# Final_6_2_1.net
KiCad netlist of a schematic drawn in EAGLE
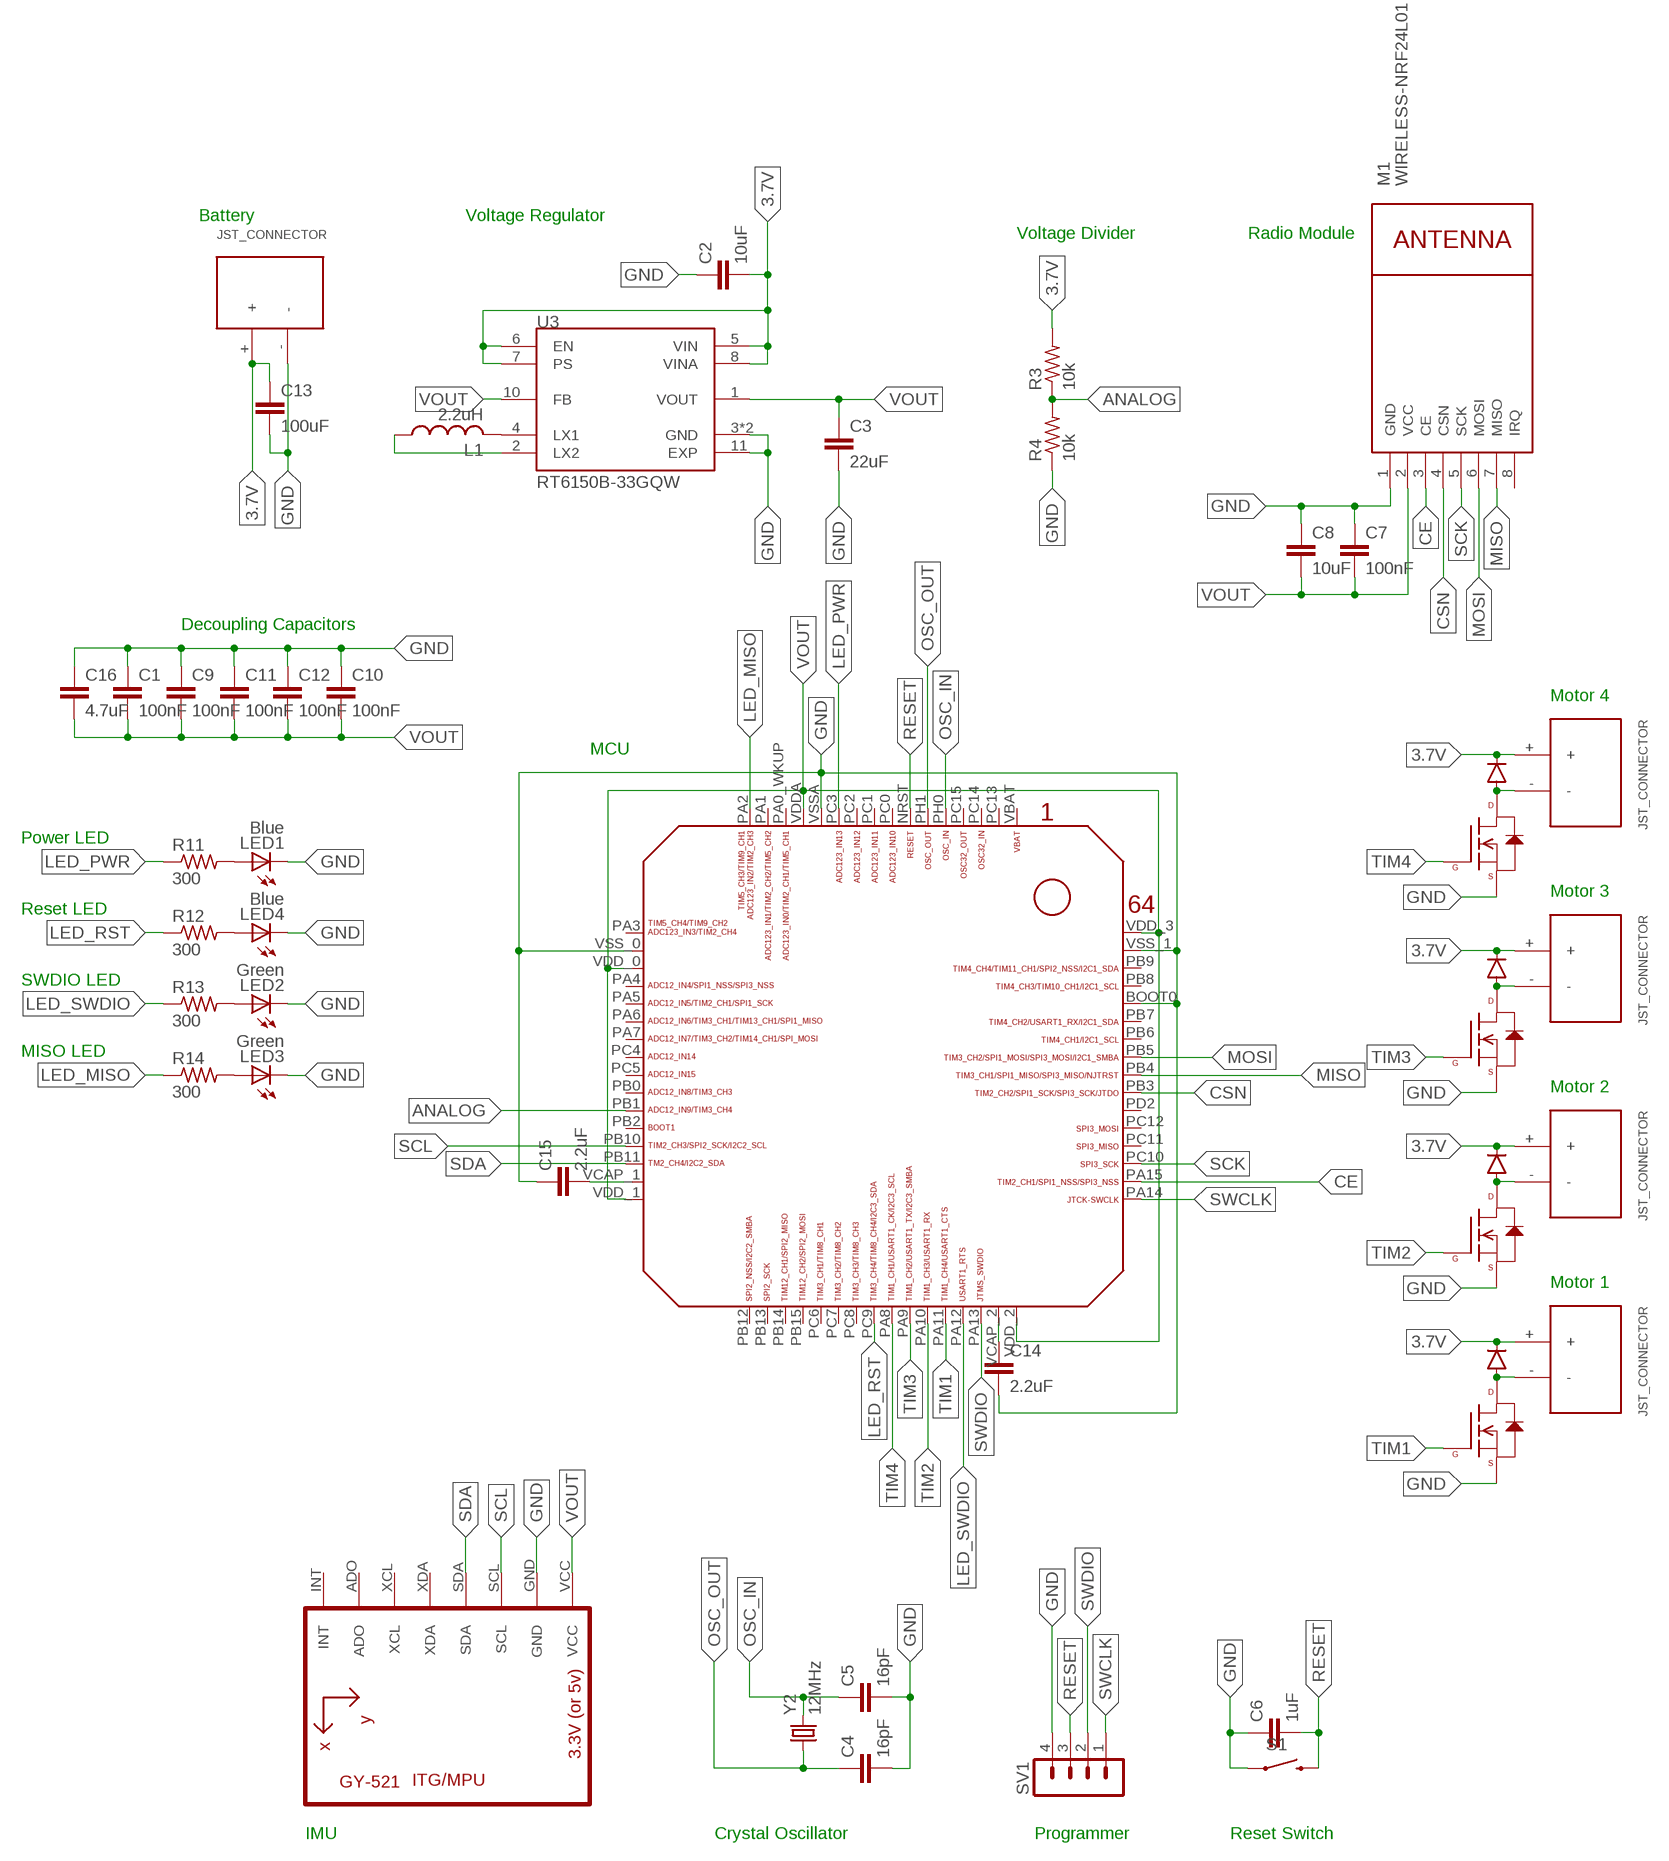
[diagram p0: schematic, sheet 1]

(export (version "E")
  (design (tool "Eeschema 10.0.6"))
  (components
    (comp (ref "C1")
      (value "100nF")
      (footprint "eagle-import:C0603")
      (libsource (lib "eagle-import") (part "rcl_334_C-EUC0603"))
    )
    (comp (ref "C2")
      (value "10uF")
      (footprint "eagle-import:C0603")
      (libsource (lib "eagle-import") (part "rcl_334_C-EUC0603"))
    )
    (comp (ref "C3")
      (value "22uF")
      (footprint "eagle-import:C0603")
      (libsource (lib "eagle-import") (part "rcl_334_C-EUC0603"))
    )
    (comp (ref "C4")
      (value "16pF")
      (footprint "eagle-import:C0603")
      (libsource (lib "eagle-import") (part "rcl_334_C-EUC0603"))
    )
    (comp (ref "C5")
      (value "16pF")
      (footprint "eagle-import:C0603")
      (libsource (lib "eagle-import") (part "rcl_334_C-EUC0603"))
    )
    (comp (ref "C6")
      (value "1uF")
      (footprint "eagle-import:C0603")
      (libsource (lib "eagle-import") (part "rcl_334_C-EUC0603"))
    )
    (comp (ref "C7")
      (value "100nF")
      (footprint "eagle-import:C0603")
      (libsource (lib "eagle-import") (part "rcl_334_C-EUC0603"))
    )
    (comp (ref "C8")
      (value "10uF")
      (footprint "eagle-import:C0603")
      (libsource (lib "eagle-import") (part "rcl_334_C-EUC0603"))
    )
    (comp (ref "C9")
      (value "100nF")
      (footprint "eagle-import:C0603")
      (libsource (lib "eagle-import") (part "rcl_334_C-EUC0603"))
    )
    (comp (ref "C10")
      (value "100nF")
      (footprint "eagle-import:C0603")
      (libsource (lib "eagle-import") (part "rcl_334_C-EUC0603"))
    )
    (comp (ref "C11")
      (value "100nF")
      (footprint "eagle-import:C0603")
      (libsource (lib "eagle-import") (part "rcl_334_C-EUC0603"))
    )
    (comp (ref "C12")
      (value "100nF")
      (footprint "eagle-import:C0603")
      (libsource (lib "eagle-import") (part "rcl_334_C-EUC0603"))
    )
    (comp (ref "C13")
      (value "100uF")
      (footprint "eagle-import:C1206")
      (libsource (lib "eagle-import") (part "rcl_334_C-EUC1206"))
    )
    (comp (ref "C14")
      (value "2.2uF")
      (footprint "eagle-import:C0603")
      (libsource (lib "eagle-import") (part "C-EUC0603"))
    )
    (comp (ref "C15")
      (value "2.2uF")
      (footprint "eagle-import:C0603")
      (libsource (lib "eagle-import") (part "C-EUC0603"))
    )
    (comp (ref "C16")
      (value "4.7uF")
      (footprint "eagle-import:C0603")
      (libsource (lib "eagle-import") (part "rcl_334_C-EUC0603"))
    )
    (comp (ref "L1")
      (value "2.2uH")
      (footprint "eagle-import:L0603")
      (libsource (lib "eagle-import") (part "L-USL0603"))
    )
    (comp (ref "LED1")
      (value "Blue")
      (footprint "eagle-import:CHIP-LED0603")
      (libsource (lib "eagle-import") (part "LEDCHIP-LED0603"))
    )
    (comp (ref "LED2")
      (value "Green")
      (footprint "eagle-import:CHIP-LED0603")
      (libsource (lib "eagle-import") (part "LEDCHIP-LED0603"))
    )
    (comp (ref "LED3")
      (value "Green")
      (footprint "eagle-import:CHIP-LED0603")
      (libsource (lib "eagle-import") (part "LEDCHIP-LED0603"))
    )
    (comp (ref "LED4")
      (value "Blue")
      (footprint "eagle-import:CHIP-LED0603")
      (libsource (lib "eagle-import") (part "LEDCHIP-LED0603"))
    )
    (comp (ref "M1")
      (value "WIRELESS-NRF24L01")
      (footprint "eagle-import:WIRELESS-NRF24L01")
      (libsource (lib "eagle-import") (part "WIRELESS-NRF24L01"))
    )
    (comp (ref "R3")
      (value "10k")
      (footprint "eagle-import:R0603")
      (libsource (lib "eagle-import") (part "R-US_R0603"))
    )
    (comp (ref "R4")
      (value "10k")
      (footprint "eagle-import:R0603")
      (libsource (lib "eagle-import") (part "R-US_R0603"))
    )
    (comp (ref "R11")
      (value "300")
      (footprint "eagle-import:R0603")
      (libsource (lib "eagle-import") (part "R-US_R0603"))
    )
    (comp (ref "R12")
      (value "300")
      (footprint "eagle-import:R0603")
      (libsource (lib "eagle-import") (part "R-US_R0603"))
    )
    (comp (ref "R13")
      (value "300")
      (footprint "eagle-import:R0603")
      (libsource (lib "eagle-import") (part "R-US_R0603"))
    )
    (comp (ref "R14")
      (value "300")
      (footprint "eagle-import:R0603")
      (libsource (lib "eagle-import") (part "R-US_R0603"))
    )
    (comp (ref "S1")
      (value "SWITCH-MOMENTARY-2SMD")
      (footprint "eagle-import:TACTILE-SWITCH-SMD")
      (libsource (lib "eagle-import") (part "SWITCH-MOMENTARY-2SMD"))
    )
    (comp (ref "SV1")
      (value "MA04-1")
      (footprint "eagle-import:MA04-1")
      (libsource (lib "eagle-import") (part "MA04-1"))
    )
    (comp (ref "U$1")
      (value "STM32F405/415_LQFP64")
      (footprint "eagle-import:STM32F405_415_LQFP64")
      (libsource (lib "eagle-import") (part "STM32F405/415_LQFP64"))
    )
    (comp (ref "U$2")
      (value "JST_CONNECTOR_FEMALE")
      (footprint "eagle-import:JST_CONNECTOR_FEMALE")
      (libsource (lib "eagle-import") (part "JST_CONNECTOR_FEMALE"))
    )
    (comp (ref "U$3")
      (value "JST_CONNECTOR_FEMALE")
      (footprint "eagle-import:JST_CONNECTOR_FEMALE")
      (libsource (lib "eagle-import") (part "JST_CONNECTOR_FEMALE"))
    )
    (comp (ref "U$4")
      (value "JST_CONNECTOR_FEMALE")
      (footprint "eagle-import:JST_CONNECTOR_FEMALE")
      (libsource (lib "eagle-import") (part "JST_CONNECTOR_FEMALE"))
    )
    (comp (ref "U$5")
      (value "JST_CONNECTOR_FEMALE")
      (footprint "eagle-import:JST_CONNECTOR_FEMALE")
      (libsource (lib "eagle-import") (part "JST_CONNECTOR_FEMALE"))
    )
    (comp (ref "U$6")
      (value "JST_CONNECTOR_FEMALE")
      (footprint "eagle-import:JST_CONNECTOR_FEMALE")
      (libsource (lib "eagle-import") (part "JST_CONNECTOR_FEMALE"))
    )
    (comp (ref "U$7")
      (value "N-CHANNEL-MOSFET-IRLML6244TRPBF")
      (footprint "eagle-import:SOT23-3")
      (libsource (lib "eagle-import") (part "N-CHANNEL-MOSFET-IRLML6244TRPBF"))
    )
    (comp (ref "U$8")
      (value "N-CHANNEL-MOSFET-IRLML6244TRPBF")
      (footprint "eagle-import:SOT23-3")
      (libsource (lib "eagle-import") (part "N-CHANNEL-MOSFET-IRLML6244TRPBF"))
    )
    (comp (ref "U$9")
      (value "N-CHANNEL-MOSFET-IRLML6244TRPBF")
      (footprint "eagle-import:SOT23-3")
      (libsource (lib "eagle-import") (part "N-CHANNEL-MOSFET-IRLML6244TRPBF"))
    )
    (comp (ref "U$10")
      (value "N-CHANNEL-MOSFET-IRLML6244TRPBF")
      (footprint "eagle-import:SOT23-3")
      (libsource (lib "eagle-import") (part "N-CHANNEL-MOSFET-IRLML6244TRPBF"))
    )
    (comp (ref "U$11")
      (value "DB2W40300L")
      (footprint "eagle-import:MINI2-F3-B")
      (libsource (lib "eagle-import") (part "DB2W40300L"))
    )
    (comp (ref "U$12")
      (value "DB2W40300L")
      (footprint "eagle-import:MINI2-F3-B")
      (libsource (lib "eagle-import") (part "DB2W40300L"))
    )
    (comp (ref "U$13")
      (value "DB2W40300L")
      (footprint "eagle-import:MINI2-F3-B")
      (libsource (lib "eagle-import") (part "DB2W40300L"))
    )
    (comp (ref "U$14")
      (value "DB2W40300L")
      (footprint "eagle-import:MINI2-F3-B")
      (libsource (lib "eagle-import") (part "DB2W40300L"))
    )
    (comp (ref "U2")
      (value "GY-521MPU6050")
      (footprint "eagle-import:GY-521")
      (libsource (lib "eagle-import") (part "GY-521MPU6050"))
    )
    (comp (ref "U3")
      (value "RT6150B-33GQW")
      (footprint "eagle-import:SON50P250X250X80-11N")
      (fields (field (name "DIGI-KEY_PART_NUMBER") "RT6150B-33GQWCT-ND") (field (name "MF") "Richtek USA"))
      (libsource (lib "eagle-import") (part "RT6150B-33GQW"))
    )
    (comp (ref "Y2")
      (value "12MHz")
      (footprint "eagle-import:HC49UP")
      (libsource (lib "eagle-import") (part "CRYSTALSMD"))
    )
  )
  (nets
    (net (code "1") (name "3.7V") (class "Default")
      (node (ref "C13") (pin "1") (pinfunction "1_1") (pintype "passive"))
      (node (ref "C2") (pin "2") (pinfunction "2_2") (pintype "passive"))
      (node (ref "R3") (pin "2") (pinfunction "2_2") (pintype "passive"))
      (node (ref "U$11") (pin "NEG") (pinfunction "GPIN_NEG") (pintype "passive"))
      (node (ref "U$12") (pin "NEG") (pinfunction "GPIN_NEG") (pintype "passive"))
      (node (ref "U$13") (pin "NEG") (pinfunction "GPIN_NEG") (pintype "passive"))
      (node (ref "U$14") (pin "NEG") (pinfunction "GPIN_NEG") (pintype "passive"))
      (node (ref "U$2") (pin "+") (pinfunction "+_+") (pintype "bidirectional"))
      (node (ref "U$3") (pin "+") (pinfunction "+_+") (pintype "bidirectional"))
      (node (ref "U$4") (pin "+") (pinfunction "+_+") (pintype "bidirectional"))
      (node (ref "U$5") (pin "+") (pinfunction "+_+") (pintype "bidirectional"))
      (node (ref "U$6") (pin "+") (pinfunction "+_+") (pintype "bidirectional"))
      (node (ref "U3") (pin "5") (pinfunction "VIN_5") (pintype "power_in"))
      (node (ref "U3") (pin "6") (pinfunction "EN_6") (pintype "input"))
      (node (ref "U3") (pin "7") (pinfunction "PS_7") (pintype "input"))
      (node (ref "U3") (pin "8") (pinfunction "VINA_8") (pintype "power_in"))
    )
    (net (code "2") (name "ANALOG") (class "Default")
      (node (ref "R3") (pin "1") (pinfunction "1_1") (pintype "passive"))
      (node (ref "R4") (pin "2") (pinfunction "2_2") (pintype "passive"))
      (node (ref "U$1") (pin "PB1") (pinfunction "PB1_PB1") (pintype "bidirectional"))
    )
    (net (code "3") (name "CE") (class "Default")
      (node (ref "M1") (pin "3") (pinfunction "CE_3") (pintype "bidirectional"))
      (node (ref "U$1") (pin "PA15") (pinfunction "PA15_PA15") (pintype "bidirectional"))
    )
    (net (code "4") (name "CSN") (class "Default")
      (node (ref "M1") (pin "4") (pinfunction "CSN_4") (pintype "bidirectional"))
      (node (ref "U$1") (pin "PB3") (pinfunction "PB3_PB3") (pintype "bidirectional"))
    )
    (net (code "5") (name "GND") (class "Default")
      (node (ref "C1") (pin "1") (pinfunction "1_1") (pintype "passive"))
      (node (ref "C10") (pin "1") (pinfunction "1_1") (pintype "passive"))
      (node (ref "C11") (pin "1") (pinfunction "1_1") (pintype "passive"))
      (node (ref "C12") (pin "1") (pinfunction "1_1") (pintype "passive"))
      (node (ref "C13") (pin "2") (pinfunction "2_2") (pintype "passive"))
      (node (ref "C14") (pin "2") (pinfunction "2_2") (pintype "passive"))
      (node (ref "C15") (pin "1") (pinfunction "1_1") (pintype "passive"))
      (node (ref "C16") (pin "1") (pinfunction "1_1") (pintype "passive"))
      (node (ref "C2") (pin "1") (pinfunction "1_1") (pintype "passive"))
      (node (ref "C3") (pin "2") (pinfunction "2_2") (pintype "passive"))
      (node (ref "C4") (pin "2") (pinfunction "2_2") (pintype "passive"))
      (node (ref "C5") (pin "2") (pinfunction "2_2") (pintype "passive"))
      (node (ref "C6") (pin "1") (pinfunction "1_1") (pintype "passive"))
      (node (ref "C7") (pin "1") (pinfunction "1_1") (pintype "passive"))
      (node (ref "C8") (pin "1") (pinfunction "1_1") (pintype "passive"))
      (node (ref "C9") (pin "1") (pinfunction "1_1") (pintype "passive"))
      (node (ref "LED1") (pin "C") (pinfunction "C_C") (pintype "passive"))
      (node (ref "LED2") (pin "C") (pinfunction "C_C") (pintype "passive"))
      (node (ref "LED3") (pin "C") (pinfunction "C_C") (pintype "passive"))
      (node (ref "LED4") (pin "C") (pinfunction "C_C") (pintype "passive"))
      (node (ref "M1") (pin "1") (pinfunction "GND_1") (pintype "power_in"))
      (node (ref "R4") (pin "1") (pinfunction "1_1") (pintype "passive"))
      (node (ref "S1") (pin "1") (pinfunction "1_1") (pintype "passive"))
      (node (ref "SV1") (pin "4") (pinfunction "4_4") (pintype "passive"))
      (node (ref "U$1") (pin "BOOT0") (pinfunction "BOOT0_BOOT0") (pintype "bidirectional"))
      (node (ref "U$1") (pin "VSSA") (pinfunction "VSSA_VSSA") (pintype "bidirectional"))
      (node (ref "U$1") (pin "VSS_0") (pinfunction "VSS_0_VSS_0") (pintype "bidirectional"))
      (node (ref "U$1") (pin "VSS_1") (pinfunction "VSS_1_VSS_1") (pintype "bidirectional"))
      (node (ref "U$10") (pin "2") (pinfunction "S_2") (pintype "passive"))
      (node (ref "U$2") (pin "-") (pinfunction "-_-") (pintype "bidirectional"))
      (node (ref "U$7") (pin "2") (pinfunction "S_2") (pintype "passive"))
      (node (ref "U$8") (pin "2") (pinfunction "S_2") (pintype "passive"))
      (node (ref "U$9") (pin "2") (pinfunction "S_2") (pintype "passive"))
      (node (ref "U2") (pin "GND") (pinfunction "GND_GND") (pintype "bidirectional"))
      (node (ref "U3") (pin "11") (pinfunction "EXP_11") (pintype "passive"))
      (node (ref "U3") (pin "3") (pinfunction "GND_3") (pintype "power_in"))
      (node (ref "U3") (pin "9") (pinfunction "GND_9") (pintype "power_in"))
    )
    (net (code "6") (name "LED_MISO") (class "Default")
      (node (ref "R14") (pin "1") (pinfunction "1_1") (pintype "passive"))
      (node (ref "U$1") (pin "PA2") (pinfunction "PA2_PA2") (pintype "bidirectional"))
    )
    (net (code "7") (name "LED_PWR") (class "Default")
      (node (ref "R11") (pin "1") (pinfunction "1_1") (pintype "passive"))
      (node (ref "U$1") (pin "PC3") (pinfunction "PC3_PC3") (pintype "bidirectional"))
    )
    (net (code "8") (name "LED_RST") (class "Default")
      (node (ref "R12") (pin "1") (pinfunction "1_1") (pintype "passive"))
      (node (ref "U$1") (pin "PC9") (pinfunction "PC9_PC9") (pintype "bidirectional"))
    )
    (net (code "9") (name "LED_SWDIO") (class "Default")
      (node (ref "R13") (pin "1") (pinfunction "1_1") (pintype "passive"))
      (node (ref "U$1") (pin "PA12") (pinfunction "PA12_PA12") (pintype "bidirectional"))
    )
    (net (code "10") (name "MISO") (class "Default")
      (node (ref "M1") (pin "7") (pinfunction "MISO_7") (pintype "bidirectional"))
      (node (ref "U$1") (pin "PB4") (pinfunction "PB4_PB4") (pintype "bidirectional"))
    )
    (net (code "11") (name "MOSI") (class "Default")
      (node (ref "M1") (pin "6") (pinfunction "MOSI_6") (pintype "bidirectional"))
      (node (ref "U$1") (pin "PB5") (pinfunction "PB5_PB5") (pintype "bidirectional"))
    )
    (net (code "12") (name "Net-(C14-Pad1)") (class "Default")
      (node (ref "C14") (pin "1") (pinfunction "1_1") (pintype "passive"))
      (node (ref "U$1") (pin "VCAP_2") (pinfunction "VCAP_2_VCAP_2") (pintype "bidirectional"))
    )
    (net (code "13") (name "Net-(C15-Pad2)") (class "Default")
      (node (ref "C15") (pin "2") (pinfunction "2_2") (pintype "passive"))
      (node (ref "U$1") (pin "VCAP_1") (pinfunction "VCAP_1_VCAP_1") (pintype "bidirectional"))
    )
    (net (code "14") (name "Net-(LED1-PadA)") (class "Default")
      (node (ref "LED1") (pin "A") (pinfunction "A_A") (pintype "passive"))
      (node (ref "R11") (pin "2") (pinfunction "2_2") (pintype "passive"))
    )
    (net (code "15") (name "Net-(LED2-PadA)") (class "Default")
      (node (ref "LED2") (pin "A") (pinfunction "A_A") (pintype "passive"))
      (node (ref "R13") (pin "2") (pinfunction "2_2") (pintype "passive"))
    )
    (net (code "16") (name "Net-(LED3-PadA)") (class "Default")
      (node (ref "LED3") (pin "A") (pinfunction "A_A") (pintype "passive"))
      (node (ref "R14") (pin "2") (pinfunction "2_2") (pintype "passive"))
    )
    (net (code "17") (name "Net-(LED4-PadA)") (class "Default")
      (node (ref "LED4") (pin "A") (pinfunction "A_A") (pintype "passive"))
      (node (ref "R12") (pin "2") (pinfunction "2_2") (pintype "passive"))
    )
    (net (code "18") (name "Net-(U$10-D)") (class "Default")
      (node (ref "U$10") (pin "3") (pinfunction "D_3") (pintype "passive"))
      (node (ref "U$14") (pin "POS") (pinfunction "PPIN_POS") (pintype "passive"))
      (node (ref "U$6") (pin "-") (pinfunction "-_-") (pintype "bidirectional"))
    )
    (net (code "19") (name "Net-(U$11-PPIN)") (class "Default")
      (node (ref "U$11") (pin "POS") (pinfunction "PPIN_POS") (pintype "passive"))
      (node (ref "U$3") (pin "-") (pinfunction "-_-") (pintype "bidirectional"))
      (node (ref "U$9") (pin "3") (pinfunction "D_3") (pintype "passive"))
    )
    (net (code "20") (name "Net-(U$12-PPIN)") (class "Default")
      (node (ref "U$12") (pin "POS") (pinfunction "PPIN_POS") (pintype "passive"))
      (node (ref "U$5") (pin "-") (pinfunction "-_-") (pintype "bidirectional"))
      (node (ref "U$8") (pin "3") (pinfunction "D_3") (pintype "passive"))
    )
    (net (code "21") (name "Net-(U$13-PPIN)") (class "Default")
      (node (ref "U$13") (pin "POS") (pinfunction "PPIN_POS") (pintype "passive"))
      (node (ref "U$4") (pin "-") (pinfunction "-_-") (pintype "bidirectional"))
      (node (ref "U$7") (pin "3") (pinfunction "D_3") (pintype "passive"))
    )
    (net (code "22") (name "Net-(U3-LX1)") (class "Default")
      (node (ref "L1") (pin "2") (pinfunction "2_2") (pintype "passive"))
      (node (ref "U3") (pin "4") (pinfunction "LX1_4") (pintype "passive"))
    )
    (net (code "23") (name "Net-(U3-LX2)") (class "Default")
      (node (ref "L1") (pin "1") (pinfunction "1_1") (pintype "passive"))
      (node (ref "U3") (pin "2") (pinfunction "LX2_2") (pintype "passive"))
    )
    (net (code "24") (name "OSC_IN") (class "Default")
      (node (ref "C5") (pin "1") (pinfunction "1_1") (pintype "passive"))
      (node (ref "U$1") (pin "PH0") (pinfunction "PH0_PH0") (pintype "bidirectional"))
      (node (ref "Y2") (pin "2") (pinfunction "2_2") (pintype "passive"))
    )
    (net (code "25") (name "OSC_OUT") (class "Default")
      (node (ref "C4") (pin "1") (pinfunction "1_1") (pintype "passive"))
      (node (ref "U$1") (pin "PH1") (pinfunction "PH1_PH1") (pintype "bidirectional"))
      (node (ref "Y2") (pin "1") (pinfunction "1_1") (pintype "passive"))
    )
    (net (code "26") (name "RESET") (class "Default")
      (node (ref "C6") (pin "2") (pinfunction "2_2") (pintype "passive"))
      (node (ref "S1") (pin "3") (pinfunction "2_3") (pintype "passive"))
      (node (ref "SV1") (pin "3") (pinfunction "3_3") (pintype "passive"))
      (node (ref "U$1") (pin "NRST") (pinfunction "NRST_NRST") (pintype "bidirectional"))
    )
    (net (code "27") (name "SCK") (class "Default")
      (node (ref "M1") (pin "5") (pinfunction "SCK_5") (pintype "bidirectional"))
      (node (ref "U$1") (pin "PC10") (pinfunction "PC10_PC10") (pintype "bidirectional"))
    )
    (net (code "28") (name "SCL") (class "Default")
      (node (ref "U$1") (pin "PB10") (pinfunction "PB10_PB10") (pintype "bidirectional"))
      (node (ref "U2") (pin "SCL") (pinfunction "SCL_SCL") (pintype "bidirectional"))
    )
    (net (code "29") (name "SDA") (class "Default")
      (node (ref "U$1") (pin "PB11") (pinfunction "PB11_PB11") (pintype "bidirectional"))
      (node (ref "U2") (pin "SDA") (pinfunction "SDA_SDA") (pintype "bidirectional"))
    )
    (net (code "30") (name "SWCLK") (class "Default")
      (node (ref "SV1") (pin "1") (pinfunction "1_1") (pintype "passive"))
      (node (ref "U$1") (pin "PA14") (pinfunction "PA14_PA14") (pintype "bidirectional"))
    )
    (net (code "31") (name "SWDIO") (class "Default")
      (node (ref "SV1") (pin "2") (pinfunction "2_2") (pintype "passive"))
      (node (ref "U$1") (pin "PA13") (pinfunction "PA13_PA13") (pintype "bidirectional"))
    )
    (net (code "32") (name "TIM1") (class "Default")
      (node (ref "U$1") (pin "PA11") (pinfunction "PA11_PA11") (pintype "bidirectional"))
      (node (ref "U$10") (pin "1") (pinfunction "G_1") (pintype "passive"))
    )
    (net (code "33") (name "TIM2") (class "Default")
      (node (ref "U$1") (pin "PA10") (pinfunction "PA10_PA10") (pintype "bidirectional"))
      (node (ref "U$8") (pin "1") (pinfunction "G_1") (pintype "passive"))
    )
    (net (code "34") (name "TIM3") (class "Default")
      (node (ref "U$1") (pin "PA9") (pinfunction "PA9_PA9") (pintype "bidirectional"))
      (node (ref "U$7") (pin "1") (pinfunction "G_1") (pintype "passive"))
    )
    (net (code "35") (name "TIM4") (class "Default")
      (node (ref "U$1") (pin "PA8") (pinfunction "PA8_PA8") (pintype "bidirectional"))
      (node (ref "U$9") (pin "1") (pinfunction "G_1") (pintype "passive"))
    )
    (net (code "36") (name "VOUT") (class "Default")
      (node (ref "C1") (pin "2") (pinfunction "2_2") (pintype "passive"))
      (node (ref "C10") (pin "2") (pinfunction "2_2") (pintype "passive"))
      (node (ref "C11") (pin "2") (pinfunction "2_2") (pintype "passive"))
      (node (ref "C12") (pin "2") (pinfunction "2_2") (pintype "passive"))
      (node (ref "C16") (pin "2") (pinfunction "2_2") (pintype "passive"))
      (node (ref "C3") (pin "1") (pinfunction "1_1") (pintype "passive"))
      (node (ref "C7") (pin "2") (pinfunction "2_2") (pintype "passive"))
      (node (ref "C8") (pin "2") (pinfunction "2_2") (pintype "passive"))
      (node (ref "C9") (pin "2") (pinfunction "2_2") (pintype "passive"))
      (node (ref "M1") (pin "2") (pinfunction "VCC_2") (pintype "power_in"))
      (node (ref "U$1") (pin "VDDA") (pinfunction "VDDA_VDDA") (pintype "bidirectional"))
      (node (ref "U$1") (pin "VDD_0") (pinfunction "VDD_0_VDD_0") (pintype "bidirectional"))
      (node (ref "U$1") (pin "VDD_1") (pinfunction "VDD_1_VDD_1") (pintype "bidirectional"))
      (node (ref "U$1") (pin "VDD_2") (pinfunction "VDD_2_VDD_2") (pintype "bidirectional"))
      (node (ref "U$1") (pin "VDD_3") (pinfunction "VDD_3_VDD_3") (pintype "bidirectional"))
      (node (ref "U2") (pin "VCC") (pinfunction "VCC_VCC") (pintype "bidirectional"))
      (node (ref "U3") (pin "1") (pinfunction "VOUT_1") (pintype "output"))
      (node (ref "U3") (pin "10") (pinfunction "FB_10") (pintype "input"))
    )
    (net (code "37") (name "unconnected-(M1-IRQ-Pad8)") (class "Default")
      (node (ref "M1") (pin "8") (pinfunction "IRQ_8") (pintype "bidirectional"))
    )
    (net (code "38") (name "unconnected-(U$1-PA0_AKUP-PadPA0_WKUP)") (class "Default")
      (node (ref "U$1") (pin "PA0_WKUP") (pinfunction "PA0_AKUP_PA0_WKUP") (pintype "bidirectional"))
    )
    (net (code "39") (name "unconnected-(U$1-PadPA1)") (class "Default")
      (node (ref "U$1") (pin "PA1") (pinfunction "PA1_PA1") (pintype "bidirectional"))
    )
    (net (code "40") (name "unconnected-(U$1-PadPA3)") (class "Default")
      (node (ref "U$1") (pin "PA3") (pinfunction "PA3_PA3") (pintype "bidirectional"))
    )
    (net (code "41") (name "unconnected-(U$1-PadPA4)") (class "Default")
      (node (ref "U$1") (pin "PA4") (pinfunction "PA4_PA4") (pintype "bidirectional"))
    )
    (net (code "42") (name "unconnected-(U$1-PadPA5)") (class "Default")
      (node (ref "U$1") (pin "PA5") (pinfunction "PA5_PA5") (pintype "bidirectional"))
    )
    (net (code "43") (name "unconnected-(U$1-PadPA6)") (class "Default")
      (node (ref "U$1") (pin "PA6") (pinfunction "PA6_PA6") (pintype "bidirectional"))
    )
    (net (code "44") (name "unconnected-(U$1-PadPA7)") (class "Default")
      (node (ref "U$1") (pin "PA7") (pinfunction "PA7_PA7") (pintype "bidirectional"))
    )
    (net (code "45") (name "unconnected-(U$1-PadPB0)") (class "Default")
      (node (ref "U$1") (pin "PB0") (pinfunction "PB0_PB0") (pintype "bidirectional"))
    )
    (net (code "46") (name "unconnected-(U$1-PadPB2)") (class "Default")
      (node (ref "U$1") (pin "PB2") (pinfunction "PB2_PB2") (pintype "bidirectional"))
    )
    (net (code "47") (name "unconnected-(U$1-PadPB6)") (class "Default")
      (node (ref "U$1") (pin "PB6") (pinfunction "PB6_PB6") (pintype "bidirectional"))
    )
    (net (code "48") (name "unconnected-(U$1-PadPB7)") (class "Default")
      (node (ref "U$1") (pin "PB7") (pinfunction "PB7_PB7") (pintype "bidirectional"))
    )
    (net (code "49") (name "unconnected-(U$1-PadPB8)") (class "Default")
      (node (ref "U$1") (pin "PB8") (pinfunction "PB8_PB8") (pintype "bidirectional"))
    )
    (net (code "50") (name "unconnected-(U$1-PadPB9)") (class "Default")
      (node (ref "U$1") (pin "PB9") (pinfunction "PB9_PB9") (pintype "bidirectional"))
    )
    (net (code "51") (name "unconnected-(U$1-PadPB12)") (class "Default")
      (node (ref "U$1") (pin "PB12") (pinfunction "PB12_PB12") (pintype "bidirectional"))
    )
    (net (code "52") (name "unconnected-(U$1-PadPB13)") (class "Default")
      (node (ref "U$1") (pin "PB13") (pinfunction "PB13_PB13") (pintype "bidirectional"))
    )
    (net (code "53") (name "unconnected-(U$1-PadPB14)") (class "Default")
      (node (ref "U$1") (pin "PB14") (pinfunction "PB14_PB14") (pintype "bidirectional"))
    )
    (net (code "54") (name "unconnected-(U$1-PadPB15)") (class "Default")
      (node (ref "U$1") (pin "PB15") (pinfunction "PB15_PB15") (pintype "bidirectional"))
    )
    (net (code "55") (name "unconnected-(U$1-PadPC0)") (class "Default")
      (node (ref "U$1") (pin "PC0") (pinfunction "PC0_PC0") (pintype "bidirectional"))
    )
    (net (code "56") (name "unconnected-(U$1-PadPC1)") (class "Default")
      (node (ref "U$1") (pin "PC1") (pinfunction "PC1_PC1") (pintype "bidirectional"))
    )
    (net (code "57") (name "unconnected-(U$1-PadPC2)") (class "Default")
      (node (ref "U$1") (pin "PC2") (pinfunction "PC2_PC2") (pintype "bidirectional"))
    )
    (net (code "58") (name "unconnected-(U$1-PadPC4)") (class "Default")
      (node (ref "U$1") (pin "PC4") (pinfunction "PC4_PC4") (pintype "bidirectional"))
    )
    (net (code "59") (name "unconnected-(U$1-PadPC5)") (class "Default")
      (node (ref "U$1") (pin "PC5") (pinfunction "PC5_PC5") (pintype "bidirectional"))
    )
    (net (code "60") (name "unconnected-(U$1-PadPC6)") (class "Default")
      (node (ref "U$1") (pin "PC6") (pinfunction "PC6_PC6") (pintype "bidirectional"))
    )
    (net (code "61") (name "unconnected-(U$1-PadPC7)") (class "Default")
      (node (ref "U$1") (pin "PC7") (pinfunction "PC7_PC7") (pintype "bidirectional"))
    )
    (net (code "62") (name "unconnected-(U$1-PadPC8)") (class "Default")
      (node (ref "U$1") (pin "PC8") (pinfunction "PC8_PC8") (pintype "bidirectional"))
    )
    (net (code "63") (name "unconnected-(U$1-PadPC11)") (class "Default")
      (node (ref "U$1") (pin "PC11") (pinfunction "PC11_PC11") (pintype "bidirectional"))
    )
    (net (code "64") (name "unconnected-(U$1-PadPC12)") (class "Default")
      (node (ref "U$1") (pin "PC12") (pinfunction "PC12_PC12") (pintype "bidirectional"))
    )
    (net (code "65") (name "unconnected-(U$1-PadPC13)") (class "Default")
      (node (ref "U$1") (pin "PC13") (pinfunction "PC13_PC13") (pintype "bidirectional"))
    )
    (net (code "66") (name "unconnected-(U$1-PadPC14)") (class "Default")
      (node (ref "U$1") (pin "PC14") (pinfunction "PC14_PC14") (pintype "bidirectional"))
    )
    (net (code "67") (name "unconnected-(U$1-PadPC15)") (class "Default")
      (node (ref "U$1") (pin "PC15") (pinfunction "PC15_PC15") (pintype "bidirectional"))
    )
    (net (code "68") (name "unconnected-(U$1-PadPD2)") (class "Default")
      (node (ref "U$1") (pin "PD2") (pinfunction "PD2_PD2") (pintype "bidirectional"))
    )
    (net (code "69") (name "unconnected-(U$1-PadVBAT)") (class "Default")
      (node (ref "U$1") (pin "VBAT") (pinfunction "VBAT_VBAT") (pintype "bidirectional"))
    )
    (net (code "70") (name "unconnected-(U2-PadADO)") (class "Default")
      (node (ref "U2") (pin "ADO") (pinfunction "ADO_ADO") (pintype "bidirectional"))
    )
    (net (code "71") (name "unconnected-(U2-PadINT)") (class "Default")
      (node (ref "U2") (pin "INT") (pinfunction "INT_INT") (pintype "bidirectional"))
    )
    (net (code "72") (name "unconnected-(U2-PadXCL)") (class "Default")
      (node (ref "U2") (pin "XCL") (pinfunction "XCL_XCL") (pintype "bidirectional"))
    )
    (net (code "73") (name "unconnected-(U2-PadXDA)") (class "Default")
      (node (ref "U2") (pin "XDA") (pinfunction "XDA_XDA") (pintype "bidirectional"))
    )
  )
)
